# LEDs.net
KiCad netlist of a schematic drawn in Altium Designer
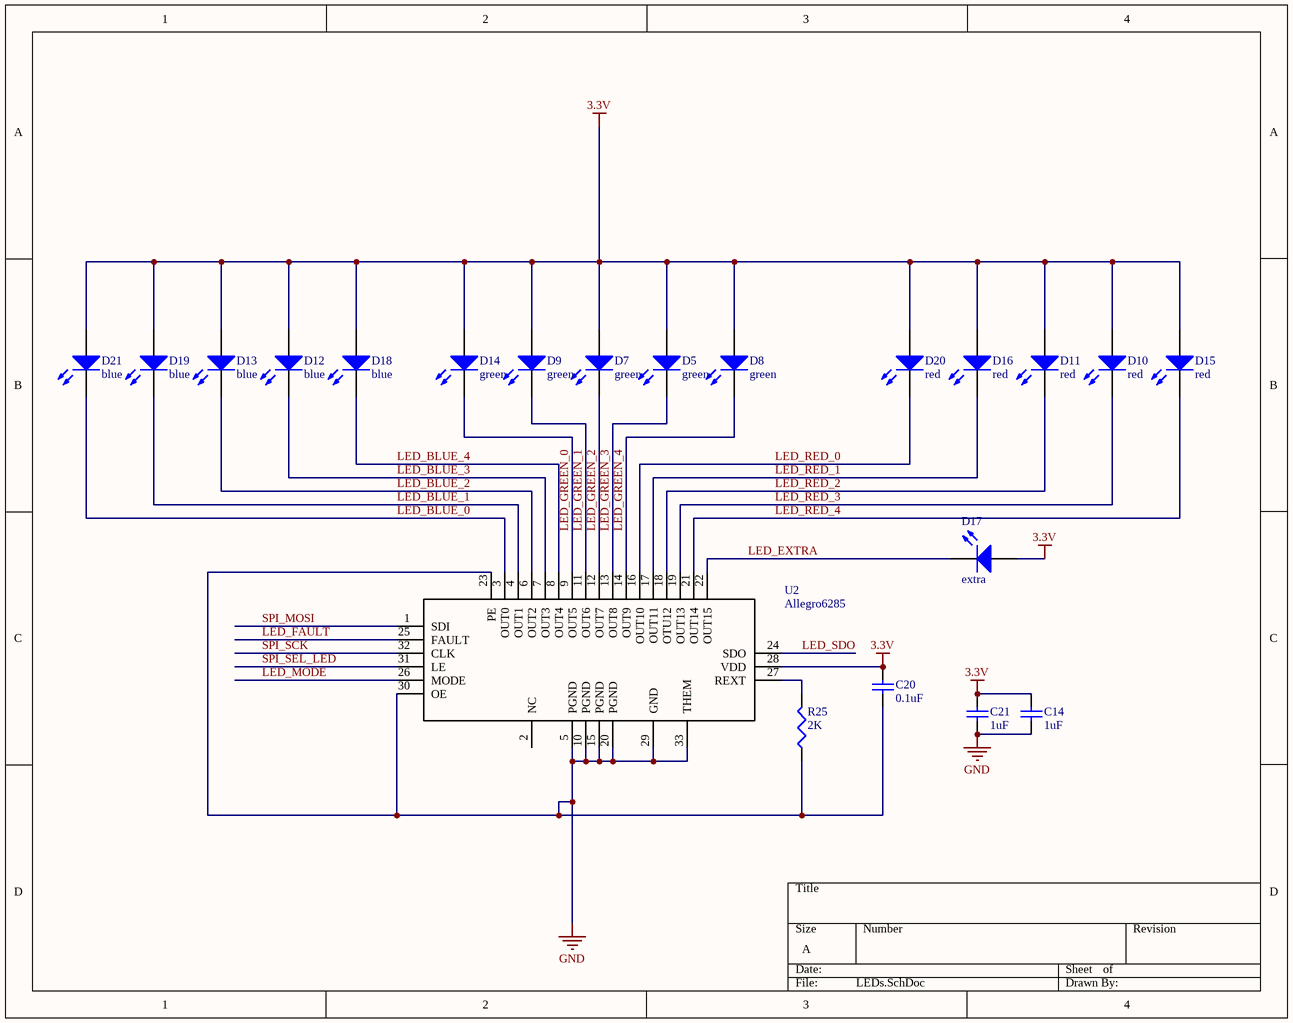
[diagram p0: LEDs.SchDoc]

(export (version "E")
  (design (tool "Eeschema 10.0.6"))
  (components
    (comp (ref "C14")
      (value "1uF")
      (footprint "CAPC1608L")
      (description "Capacitor (Semiconductor SIM Model)")
      (fields (field (name "Comment") "Cap Semi") (field (name "PUBLISHER") "Altium Limited"))
      (libsource (lib "Miscellaneous Devices") (part "Cap Semi"))
    )
    (comp (ref "C20")
      (value "0.1uF")
      (footprint "CAPC1005L")
      (description "Capacitor (Semiconductor SIM Model)")
      (fields (field (name "Comment") "Cap Semi") (field (name "PUBLISHER") "Altium Limited"))
      (libsource (lib "Miscellaneous Devices") (part "Cap Semi"))
    )
    (comp (ref "C21")
      (value "1uF")
      (footprint "CAPC1608L")
      (description "Capacitor (Semiconductor SIM Model)")
      (fields (field (name "Comment") "Cap Semi") (field (name "PUBLISHER") "Altium Limited"))
      (libsource (lib "Miscellaneous Devices") (part "Cap Semi"))
    )
    (comp (ref "D5") (value "green") (footprint "SurfaceMount(603)") (libsource (lib "mrone") (part "LED")))
    (comp (ref "D7") (value "green") (footprint "SurfaceMount(603)") (libsource (lib "mrone") (part "LED")))
    (comp (ref "D8") (value "green") (footprint "SurfaceMount(603)") (libsource (lib "mrone") (part "LED")))
    (comp (ref "D9") (value "green") (footprint "SurfaceMount(603)") (libsource (lib "mrone") (part "LED")))
    (comp (ref "D10") (value "red") (footprint "SurfaceMount(603)") (libsource (lib "mrone") (part "LED")))
    (comp (ref "D11") (value "red") (footprint "SurfaceMount(603)") (libsource (lib "mrone") (part "LED")))
    (comp (ref "D12") (value "blue") (footprint "SurfaceMount(603)") (libsource (lib "mrone") (part "LED")))
    (comp (ref "D13") (value "blue") (footprint "SurfaceMount(603)") (libsource (lib "mrone") (part "LED")))
    (comp (ref "D14") (value "green") (footprint "SurfaceMount(603)") (libsource (lib "mrone") (part "LED")))
    (comp (ref "D15") (value "red") (footprint "SurfaceMount(603)") (libsource (lib "mrone") (part "LED")))
    (comp (ref "D16") (value "red") (footprint "SurfaceMount(603)") (libsource (lib "mrone") (part "LED")))
    (comp (ref "D17") (value "extra") (footprint "SurfaceMount(603)") (libsource (lib "") (part "LED_1")))
    (comp (ref "D18") (value "blue") (footprint "SurfaceMount(603)") (libsource (lib "mrone") (part "LED")))
    (comp (ref "D19") (value "blue") (footprint "SurfaceMount(603)") (libsource (lib "mrone") (part "LED")))
    (comp (ref "D20") (value "red") (footprint "SurfaceMount(603)") (libsource (lib "mrone") (part "LED")))
    (comp (ref "D21") (value "blue") (footprint "SurfaceMount(603)") (libsource (lib "mrone") (part "LED")))
    (comp (ref "R25")
      (value "2K")
      (footprint "RESC1608L")
      (description "Resistor")
      (fields (field (name "Comment") "Res3") (field (name "PUBLISHER") "Altium Limited"))
      (libsource (lib "Miscellaneous Devices") (part "Res3"))
    )
    (comp (ref "U2")
      (value "Allegro6285")
      (footprint "QFN-32")
      (libsource (lib "mrone") (part "Allegro6285"))
    )
  )
  (nets
    (net (code "1") (name "/LED_BLUE_0") (class "Default")
      (node (ref "D21") (pin "2") (pinfunction "K_2") (pintype "passive"))
      (node (ref "U2") (pin "3") (pinfunction "OUT0_3") (pintype "passive"))
    )
    (net (code "2") (name "/LED_BLUE_1") (class "Default")
      (node (ref "D19") (pin "2") (pinfunction "K_2") (pintype "passive"))
      (node (ref "U2") (pin "4") (pinfunction "OUT1_4") (pintype "passive"))
    )
    (net (code "3") (name "/LED_BLUE_2") (class "Default")
      (node (ref "D13") (pin "2") (pinfunction "K_2") (pintype "passive"))
      (node (ref "U2") (pin "6") (pinfunction "OUT2_6") (pintype "passive"))
    )
    (net (code "4") (name "/LED_BLUE_3") (class "Default")
      (node (ref "D12") (pin "2") (pinfunction "K_2") (pintype "passive"))
      (node (ref "U2") (pin "7") (pinfunction "OUT3_7") (pintype "passive"))
    )
    (net (code "5") (name "/LED_BLUE_4") (class "Default")
      (node (ref "D18") (pin "2") (pinfunction "K_2") (pintype "passive"))
      (node (ref "U2") (pin "8") (pinfunction "OUT4_8") (pintype "passive"))
    )
    (net (code "6") (name "/LED_EXTRA") (class "Default")
      (node (ref "D17") (pin "2") (pinfunction "K_2") (pintype "passive"))
      (node (ref "U2") (pin "22") (pinfunction "OUT15_22") (pintype "passive"))
    )
    (net (code "7") (name "/LED_FAULT") (class "Default")
      (node (ref "U2") (pin "25") (pinfunction "FAULT_25") (pintype "passive"))
    )
    (net (code "8") (name "/LED_GREEN_0") (class "Default")
      (node (ref "D14") (pin "2") (pinfunction "K_2") (pintype "passive"))
      (node (ref "U2") (pin "9") (pinfunction "OUT5_9") (pintype "passive"))
    )
    (net (code "9") (name "/LED_GREEN_1") (class "Default")
      (node (ref "D9") (pin "2") (pinfunction "K_2") (pintype "passive"))
      (node (ref "U2") (pin "11") (pinfunction "OUT6_11") (pintype "passive"))
    )
    (net (code "10") (name "/LED_GREEN_2") (class "Default")
      (node (ref "D7") (pin "2") (pinfunction "K_2") (pintype "passive"))
      (node (ref "U2") (pin "12") (pinfunction "OUT7_12") (pintype "passive"))
    )
    (net (code "11") (name "/LED_GREEN_3") (class "Default")
      (node (ref "D5") (pin "2") (pinfunction "K_2") (pintype "passive"))
      (node (ref "U2") (pin "13") (pinfunction "OUT8_13") (pintype "passive"))
    )
    (net (code "12") (name "/LED_GREEN_4") (class "Default")
      (node (ref "D8") (pin "2") (pinfunction "K_2") (pintype "passive"))
      (node (ref "U2") (pin "14") (pinfunction "OUT9_14") (pintype "passive"))
    )
    (net (code "13") (name "/LED_MODE") (class "Default")
      (node (ref "U2") (pin "26") (pinfunction "MODE_26") (pintype "passive"))
    )
    (net (code "14") (name "/LED_RED_0") (class "Default")
      (node (ref "D20") (pin "2") (pinfunction "K_2") (pintype "passive"))
      (node (ref "U2") (pin "16") (pinfunction "OUT10_16") (pintype "passive"))
    )
    (net (code "15") (name "/LED_RED_1") (class "Default")
      (node (ref "D16") (pin "2") (pinfunction "K_2") (pintype "passive"))
      (node (ref "U2") (pin "17") (pinfunction "OUT11_17") (pintype "passive"))
    )
    (net (code "16") (name "/LED_RED_2") (class "Default")
      (node (ref "D11") (pin "2") (pinfunction "K_2") (pintype "passive"))
      (node (ref "U2") (pin "18") (pinfunction "OTU12_18") (pintype "passive"))
    )
    (net (code "17") (name "/LED_RED_3") (class "Default")
      (node (ref "D10") (pin "2") (pinfunction "K_2") (pintype "passive"))
      (node (ref "U2") (pin "19") (pinfunction "OUT13_19") (pintype "passive"))
    )
    (net (code "18") (name "/LED_RED_4") (class "Default")
      (node (ref "D15") (pin "2") (pinfunction "K_2") (pintype "passive"))
      (node (ref "U2") (pin "21") (pinfunction "OUT14_21") (pintype "passive"))
    )
    (net (code "19") (name "/LED_SDO") (class "Default")
      (node (ref "U2") (pin "24") (pinfunction "SDO_24") (pintype "passive"))
    )
    (net (code "20") (name "/SPI_MOSI") (class "Default")
      (node (ref "U2") (pin "1") (pinfunction "SDI_1") (pintype "passive"))
    )
    (net (code "21") (name "/SPI_SCK") (class "Default")
      (node (ref "U2") (pin "32") (pinfunction "CLK_32") (pintype "passive"))
    )
    (net (code "22") (name "/SPI_SEL_LED") (class "Default")
      (node (ref "U2") (pin "31") (pinfunction "LE_31") (pintype "passive"))
    )
    (net (code "23") (name "3.3V") (class "Default")
      (node (ref "C14") (pin "2") (pinfunction "2_2") (pintype "passive"))
      (node (ref "C20") (pin "2") (pinfunction "2_2") (pintype "passive"))
      (node (ref "C21") (pin "2") (pinfunction "2_2") (pintype "passive"))
      (node (ref "D10") (pin "1") (pinfunction "A_1") (pintype "passive"))
      (node (ref "D11") (pin "1") (pinfunction "A_1") (pintype "passive"))
      (node (ref "D12") (pin "1") (pinfunction "A_1") (pintype "passive"))
      (node (ref "D13") (pin "1") (pinfunction "A_1") (pintype "passive"))
      (node (ref "D14") (pin "1") (pinfunction "A_1") (pintype "passive"))
      (node (ref "D15") (pin "1") (pinfunction "A_1") (pintype "passive"))
      (node (ref "D16") (pin "1") (pinfunction "A_1") (pintype "passive"))
      (node (ref "D17") (pin "1") (pinfunction "A_1") (pintype "passive"))
      (node (ref "D18") (pin "1") (pinfunction "A_1") (pintype "passive"))
      (node (ref "D19") (pin "1") (pinfunction "A_1") (pintype "passive"))
      (node (ref "D20") (pin "1") (pinfunction "A_1") (pintype "passive"))
      (node (ref "D21") (pin "1") (pinfunction "A_1") (pintype "passive"))
      (node (ref "D5") (pin "1") (pinfunction "A_1") (pintype "passive"))
      (node (ref "D7") (pin "1") (pinfunction "A_1") (pintype "passive"))
      (node (ref "D8") (pin "1") (pinfunction "A_1") (pintype "passive"))
      (node (ref "D9") (pin "1") (pinfunction "A_1") (pintype "passive"))
      (node (ref "U2") (pin "28") (pinfunction "VDD_28") (pintype "passive"))
    )
    (net (code "24") (name "GND") (class "Default")
      (node (ref "C14") (pin "1") (pinfunction "1_1") (pintype "passive"))
      (node (ref "C20") (pin "1") (pinfunction "1_1") (pintype "passive"))
      (node (ref "C21") (pin "1") (pinfunction "1_1") (pintype "passive"))
      (node (ref "R25") (pin "1") (pinfunction "1_1") (pintype "passive"))
      (node (ref "U2") (pin "10") (pinfunction "PGND_10") (pintype "passive"))
      (node (ref "U2") (pin "15") (pinfunction "PGND_15") (pintype "passive"))
      (node (ref "U2") (pin "20") (pinfunction "PGND_20") (pintype "passive"))
      (node (ref "U2") (pin "23") (pinfunction "PE_23") (pintype "passive"))
      (node (ref "U2") (pin "29") (pinfunction "GND_29") (pintype "passive"))
      (node (ref "U2") (pin "30") (pinfunction "OE_30") (pintype "passive"))
      (node (ref "U2") (pin "33") (pinfunction "THEM_33") (pintype "passive"))
      (node (ref "U2") (pin "5") (pinfunction "PGND_5") (pintype "passive"))
    )
    (net (code "25") (name "Net-(U2-REXT)") (class "Default")
      (node (ref "R25") (pin "2") (pinfunction "2_2") (pintype "passive"))
      (node (ref "U2") (pin "27") (pinfunction "REXT_27") (pintype "passive"))
    )
    (net (code "26") (name "unconnected-(U2-NC-Pad2)") (class "Default")
      (node (ref "U2") (pin "2") (pinfunction "NC_2") (pintype "passive"))
    )
  )
)
